# MCU.net
KiCad netlist of a schematic drawn in Altium Designer
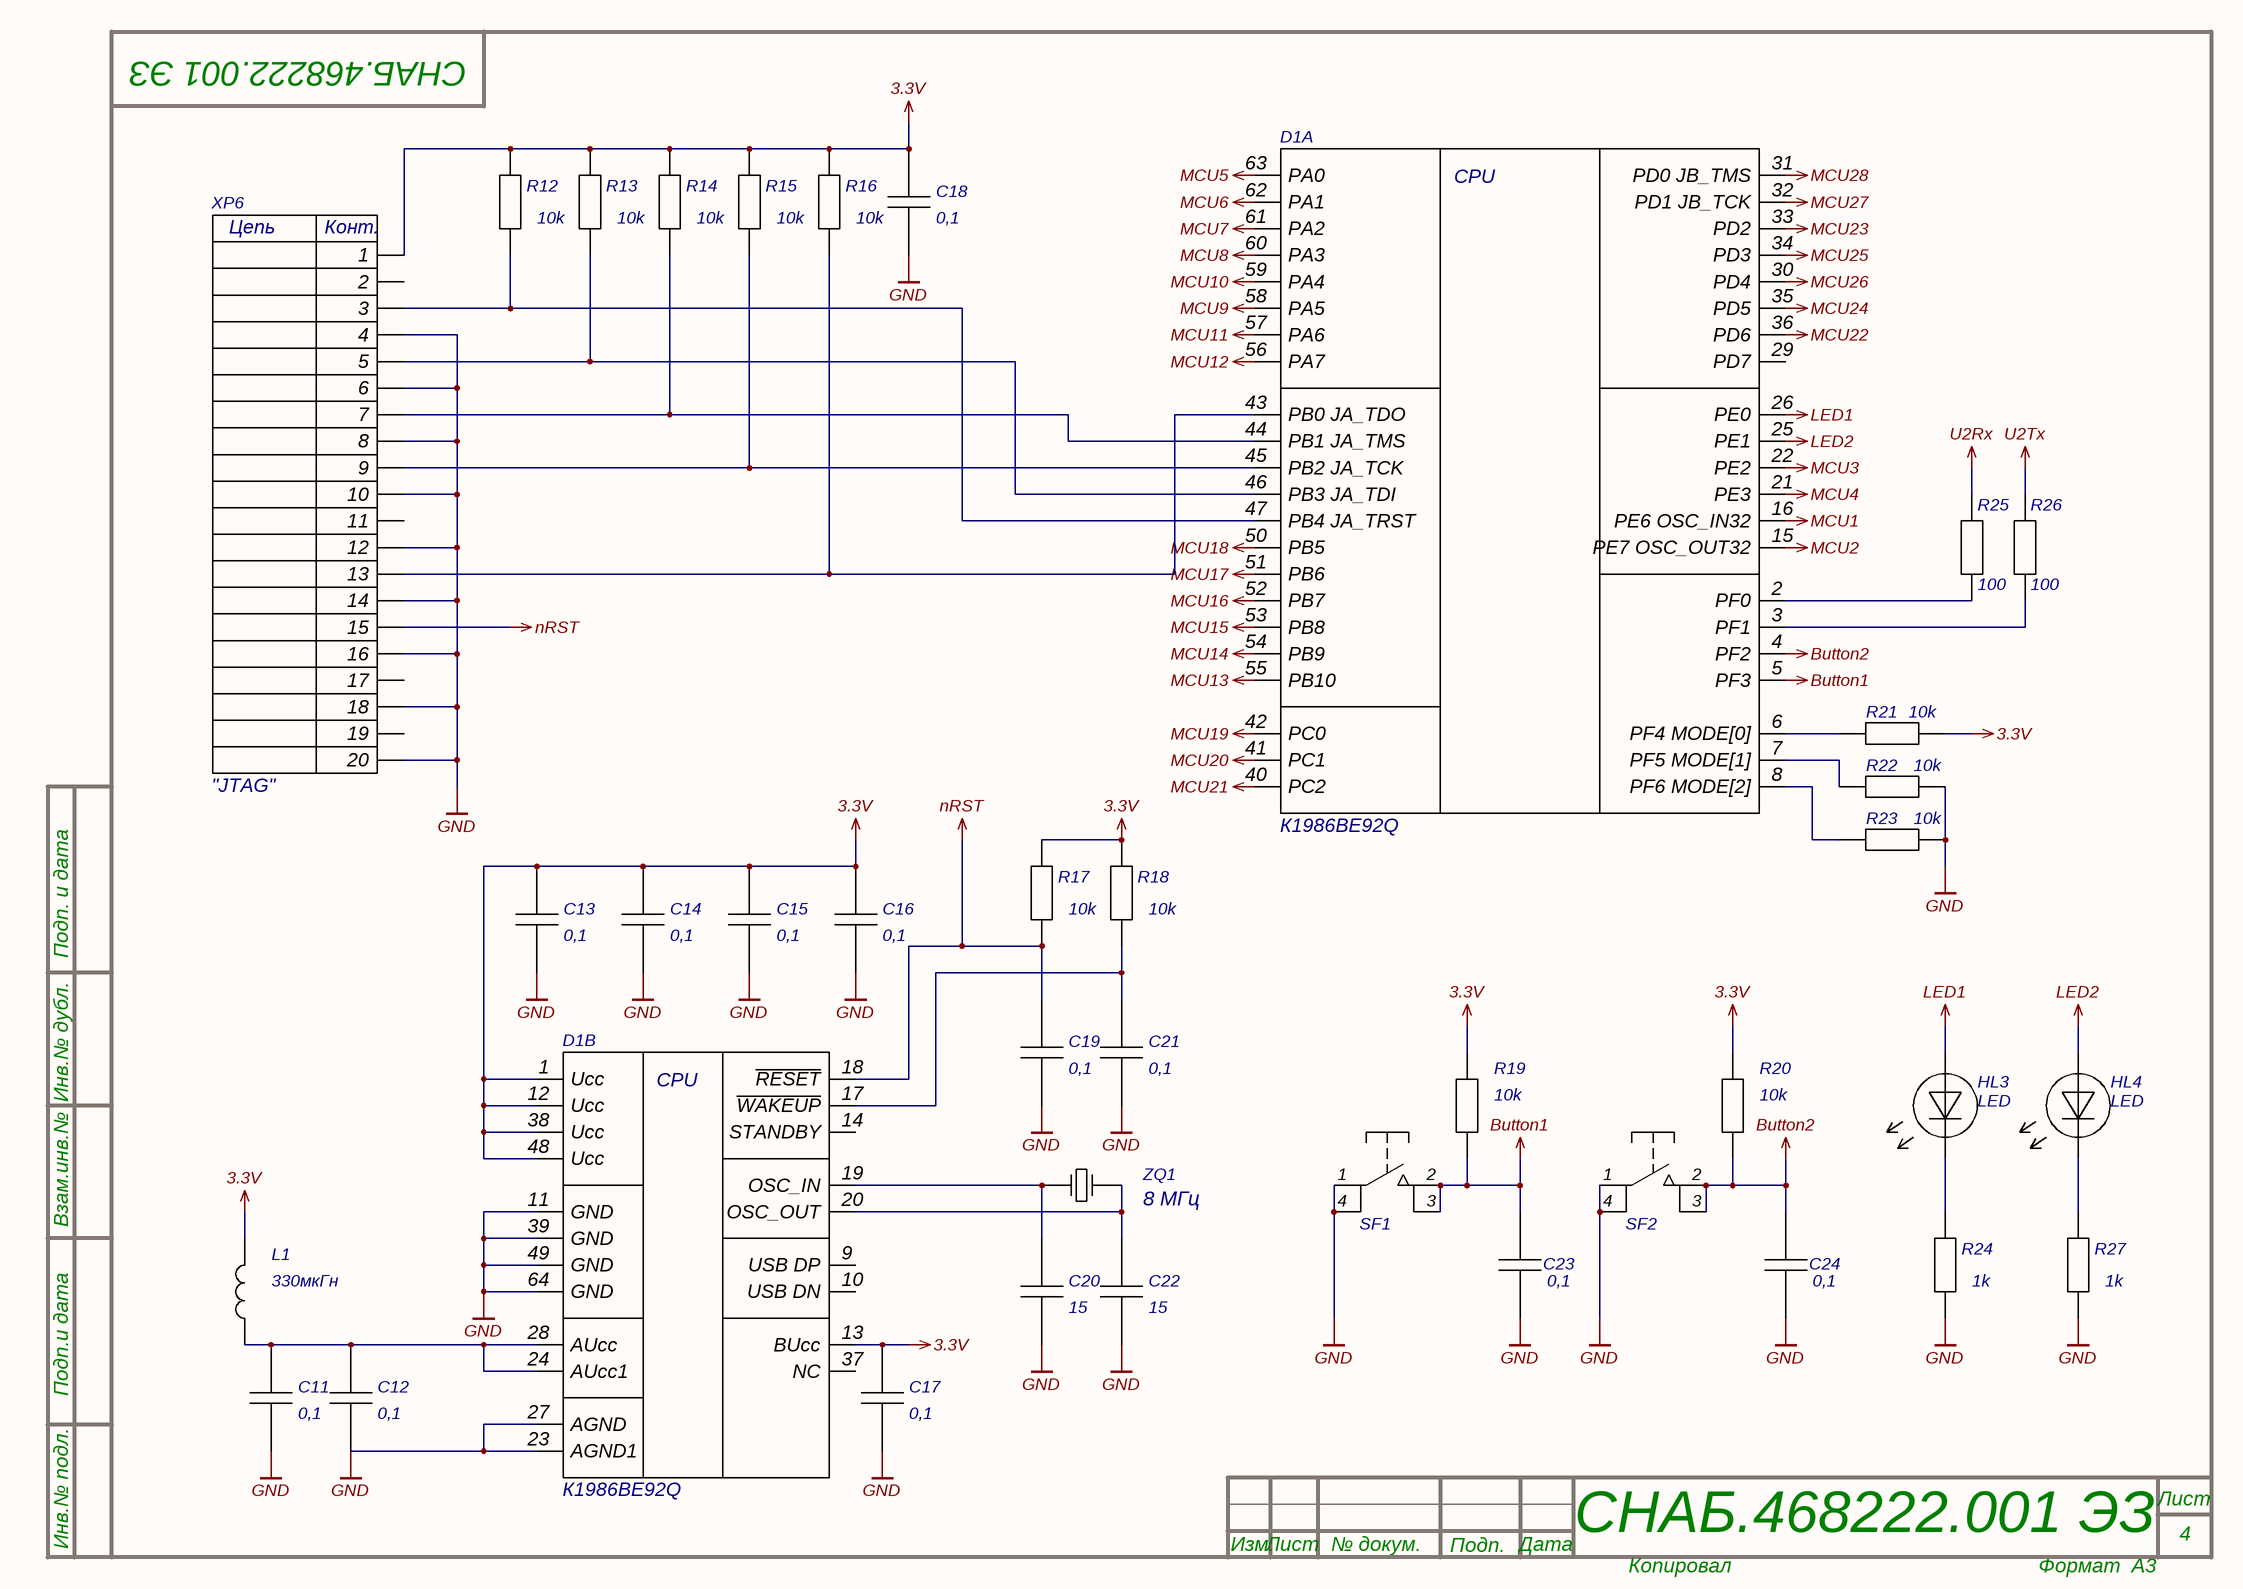
[diagram p0: MCU.SchDoc]

(export (version "E")
  (design (tool "Eeschema 10.0.6"))
  (components
    (comp (ref "C11")
      (value "0,1")
      (footprint "C0603")
      (description "Чип-конденсатор")
      (libsource (lib "Passive") (part "Chip Capasitor"))
    )
    (comp (ref "C12")
      (value "0,1")
      (footprint "C0603")
      (description "Чип-конденсатор")
      (libsource (lib "Passive") (part "Chip Capasitor"))
    )
    (comp (ref "C13")
      (value "0,1")
      (footprint "C0603")
      (description "Чип-конденсатор")
      (libsource (lib "Passive") (part "Chip Capasitor"))
    )
    (comp (ref "C14")
      (value "0,1")
      (footprint "C0603")
      (description "Чип-конденсатор")
      (libsource (lib "Passive") (part "Chip Capasitor"))
    )
    (comp (ref "C15")
      (value "0,1")
      (footprint "C0603")
      (description "Чип-конденсатор")
      (libsource (lib "Passive") (part "Chip Capasitor"))
    )
    (comp (ref "C16")
      (value "0,1")
      (footprint "C0603")
      (description "Чип-конденсатор")
      (libsource (lib "Passive") (part "Chip Capasitor"))
    )
    (comp (ref "C17")
      (value "0,1")
      (footprint "C0603")
      (description "Чип-конденсатор")
      (libsource (lib "Passive") (part "Chip Capasitor"))
    )
    (comp (ref "C18")
      (value "0,1")
      (footprint "C0603")
      (description "Чип-конденсатор")
      (libsource (lib "Passive") (part "Chip Capasitor"))
    )
    (comp (ref "C19")
      (value "0,1")
      (footprint "C0603")
      (description "Чип-конденсатор")
      (libsource (lib "Passive") (part "Chip Capasitor"))
    )
    (comp (ref "C20")
      (value "15")
      (footprint "C0603")
      (description "Чип-конденсатор")
      (libsource (lib "Passive") (part "Chip Capasitor"))
    )
    (comp (ref "C21")
      (value "0,1")
      (footprint "C0603")
      (description "Чип-конденсатор")
      (libsource (lib "Passive") (part "Chip Capasitor"))
    )
    (comp (ref "C22")
      (value "15")
      (footprint "C0603")
      (description "Чип-конденсатор")
      (libsource (lib "Passive") (part "Chip Capasitor"))
    )
    (comp (ref "C23")
      (value "0,1")
      (footprint "C0603")
      (description "Чип-конденсатор")
      (libsource (lib "Passive") (part "Chip Capasitor"))
    )
    (comp (ref "C24")
      (value "0,1")
      (footprint "C0603")
      (description "Чип-конденсатор")
      (libsource (lib "Passive") (part "Chip Capasitor"))
    )
    (comp (ref "D1")
      (value "К1986ВЕ92Q")
      (footprint "LQFP64")
      (description "32бит микроконтроллер CortexM3")
      (fields (field (name "MANUFACTURER") "АО «ПКК Миландр»"))
      (libsource (lib "Schlib") (part "К1986ВЕ92QI(C)_2parts(LQFP64)"))
    )
    (comp (ref "HL3")
      (value "LED")
      (footprint "LED 5mm (L-7113IT)")
      (description "Светодиод, d=5мм")
      (fields (field (name "MANUFACTURER") "Kingbright"))
      (libsource (lib "Schlib") (part "LED"))
    )
    (comp (ref "HL4")
      (value "LED")
      (footprint "LED 5mm (L-7113IT)")
      (description "Светодиод, d=5мм")
      (fields (field (name "MANUFACTURER") "Kingbright"))
      (libsource (lib "Schlib") (part "LED"))
    )
    (comp (ref "L1")
      (value "330мкГн")
      (footprint "LQH43M (1812)")
      (description "Чип-индуктивность 95мА, 330мкГн 10%")
      (fields (field (name "MANUFACTURER") "Murata Electronics"))
      (libsource (lib "Schlib") (part "LQH43MN331K"))
    )
    (comp (ref "R12")
      (value "10k")
      (footprint "R0805")
      (description "Чип-резистор")
      (libsource (lib "Passive") (part "Chip Resistor"))
    )
    (comp (ref "R13")
      (value "10k")
      (footprint "R0805")
      (description "Чип-резистор")
      (libsource (lib "Passive") (part "Chip Resistor"))
    )
    (comp (ref "R14")
      (value "10k")
      (footprint "R0805")
      (description "Чип-резистор")
      (libsource (lib "Passive") (part "Chip Resistor"))
    )
    (comp (ref "R15")
      (value "10k")
      (footprint "R0805")
      (description "Чип-резистор")
      (libsource (lib "Passive") (part "Chip Resistor"))
    )
    (comp (ref "R16")
      (value "10k")
      (footprint "R0805")
      (description "Чип-резистор")
      (libsource (lib "Passive") (part "Chip Resistor"))
    )
    (comp (ref "R17")
      (value "10k")
      (footprint "R0805")
      (description "Чип-резистор")
      (libsource (lib "Passive") (part "Chip Resistor"))
    )
    (comp (ref "R18")
      (value "10k")
      (footprint "R0805")
      (description "Чип-резистор")
      (libsource (lib "Passive") (part "Chip Resistor"))
    )
    (comp (ref "R19")
      (value "10k")
      (footprint "R0603")
      (description "Чип-резистор")
      (libsource (lib "") (part "Chip Resistor_1"))
    )
    (comp (ref "R20")
      (value "10k")
      (footprint "R0603")
      (description "Чип-резистор")
      (libsource (lib "") (part "Chip Resistor_1"))
    )
    (comp (ref "R21")
      (value "10k")
      (footprint "R0805")
      (description "Чип-резистор")
      (libsource (lib "") (part "Chip Resistor_2"))
    )
    (comp (ref "R22")
      (value "10k")
      (footprint "R0805")
      (description "Чип-резистор")
      (libsource (lib "") (part "Chip Resistor_2"))
    )
    (comp (ref "R23")
      (value "10k")
      (footprint "R0805")
      (description "Чип-резистор")
      (libsource (lib "") (part "Chip Resistor_2"))
    )
    (comp (ref "R24")
      (value "1k")
      (footprint "R0805")
      (description "Чип-резистор")
      (libsource (lib "Passive") (part "Chip Resistor"))
    )
    (comp (ref "R25")
      (value "100")
      (footprint "R0805")
      (description "Чип-резистор")
      (libsource (lib "Passive") (part "Chip Resistor"))
    )
    (comp (ref "R26")
      (value "100")
      (footprint "R0805")
      (description "Чип-резистор")
      (libsource (lib "Passive") (part "Chip Resistor"))
    )
    (comp (ref "R27")
      (value "1k")
      (footprint "R0805")
      (description "Чип-резистор")
      (libsource (lib "Passive") (part "Chip Resistor"))
    )
    (comp (ref "SF1")
      (value "0650HIM-130G-G")
      (footprint "TC-0103")
      (description "Кнопка тактовая, h=5мм")
      (fields (field (name "MANUFACTURER") "Switronic Industrial"))
      (libsource (lib "Schlib") (part "0650HIM-130G-G"))
    )
    (comp (ref "SF2")
      (value "0650HIM-130G-G")
      (footprint "TC-0103")
      (description "Кнопка тактовая, h=5мм")
      (fields (field (name "MANUFACTURER") "Switronic Industrial"))
      (libsource (lib "Schlib") (part "0650HIM-130G-G"))
    )
    (comp (ref "XP6")
      (value "\"JTAG\"")
      (footprint "IDC_20")
      (description "J-TAG Connector")
      (libsource (lib "Schlib") (part "JTAG_20 L"))
    )
    (comp (ref "ZQ1")
      (value "8 МГц")
      (footprint "HC-49SM")
      (description "Кварцевый резонатор, 8 МГц")
      (fields (field (name "MANUFACTURER") "SJK"))
      (libsource (lib "Schlib") (part "QuartzRes"))
    )
  )
  (nets
    (net (code "1") (name "3.3V") (class "Default")
      (node (ref "C13") (pin "2") (pinfunction "2_2") (pintype "passive"))
      (node (ref "C14") (pin "2") (pinfunction "2_2") (pintype "passive"))
      (node (ref "C15") (pin "2") (pinfunction "2_2") (pintype "passive"))
      (node (ref "C16") (pin "2") (pinfunction "2_2") (pintype "passive"))
      (node (ref "C17") (pin "2") (pinfunction "2_2") (pintype "passive"))
      (node (ref "C18") (pin "2") (pinfunction "2_2") (pintype "passive"))
      (node (ref "D1") (pin "1") (pinfunction "Ucc_1") (pintype "passive"))
      (node (ref "D1") (pin "12") (pinfunction "Ucc_12") (pintype "passive"))
      (node (ref "D1") (pin "13") (pinfunction "BUcc_13") (pintype "passive"))
      (node (ref "D1") (pin "38") (pinfunction "Ucc_38") (pintype "passive"))
      (node (ref "D1") (pin "48") (pinfunction "Ucc_48") (pintype "passive"))
      (node (ref "L1") (pin "2") (pinfunction "2_2") (pintype "passive"))
      (node (ref "R12") (pin "2") (pinfunction "2_2") (pintype "passive"))
      (node (ref "R13") (pin "2") (pinfunction "2_2") (pintype "passive"))
      (node (ref "R14") (pin "2") (pinfunction "2_2") (pintype "passive"))
      (node (ref "R15") (pin "2") (pinfunction "2_2") (pintype "passive"))
      (node (ref "R16") (pin "2") (pinfunction "2_2") (pintype "passive"))
      (node (ref "R17") (pin "2") (pinfunction "2_2") (pintype "passive"))
      (node (ref "R18") (pin "2") (pinfunction "2_2") (pintype "passive"))
      (node (ref "R19") (pin "1") (pinfunction "1_1") (pintype "passive"))
      (node (ref "R20") (pin "1") (pinfunction "1_1") (pintype "passive"))
      (node (ref "R21") (pin "2") (pinfunction "2_2") (pintype "passive"))
      (node (ref "XP6") (pin "1") (pinfunction "1_1") (pintype "passive"))
    )
    (net (code "2") (name "Button1") (class "Default")
      (node (ref "C23") (pin "2") (pinfunction "2_2") (pintype "passive"))
      (node (ref "D1") (pin "5") (pinfunction "PF3_5") (pintype "passive"))
      (node (ref "R19") (pin "2") (pinfunction "2_2") (pintype "passive"))
      (node (ref "SF1") (pin "2") (pinfunction "2_2") (pintype "passive"))
      (node (ref "SF1") (pin "3") (pinfunction "3_3") (pintype "passive"))
    )
    (net (code "3") (name "Button2") (class "Default")
      (node (ref "C24") (pin "2") (pinfunction "2_2") (pintype "passive"))
      (node (ref "D1") (pin "4") (pinfunction "PF2_4") (pintype "passive"))
      (node (ref "R20") (pin "2") (pinfunction "2_2") (pintype "passive"))
      (node (ref "SF2") (pin "2") (pinfunction "2_2") (pintype "passive"))
      (node (ref "SF2") (pin "3") (pinfunction "3_3") (pintype "passive"))
    )
    (net (code "4") (name "GND") (class "Default")
      (node (ref "C11") (pin "1") (pinfunction "1_1") (pintype "passive"))
      (node (ref "C12") (pin "1") (pinfunction "1_1") (pintype "passive"))
      (node (ref "C13") (pin "1") (pinfunction "1_1") (pintype "passive"))
      (node (ref "C14") (pin "1") (pinfunction "1_1") (pintype "passive"))
      (node (ref "C15") (pin "1") (pinfunction "1_1") (pintype "passive"))
      (node (ref "C16") (pin "1") (pinfunction "1_1") (pintype "passive"))
      (node (ref "C17") (pin "1") (pinfunction "1_1") (pintype "passive"))
      (node (ref "C18") (pin "1") (pinfunction "1_1") (pintype "passive"))
      (node (ref "C19") (pin "1") (pinfunction "1_1") (pintype "passive"))
      (node (ref "C20") (pin "1") (pinfunction "1_1") (pintype "passive"))
      (node (ref "C21") (pin "1") (pinfunction "1_1") (pintype "passive"))
      (node (ref "C22") (pin "1") (pinfunction "1_1") (pintype "passive"))
      (node (ref "C23") (pin "1") (pinfunction "1_1") (pintype "passive"))
      (node (ref "C24") (pin "1") (pinfunction "1_1") (pintype "passive"))
      (node (ref "D1") (pin "11") (pinfunction "GND_11") (pintype "passive"))
      (node (ref "D1") (pin "23") (pinfunction "AGND1_23") (pintype "passive"))
      (node (ref "D1") (pin "27") (pinfunction "AGND_27") (pintype "passive"))
      (node (ref "D1") (pin "39") (pinfunction "GND_39") (pintype "passive"))
      (node (ref "D1") (pin "49") (pinfunction "GND_49") (pintype "passive"))
      (node (ref "D1") (pin "64") (pinfunction "GND_64") (pintype "passive"))
      (node (ref "R22") (pin "2") (pinfunction "2_2") (pintype "passive"))
      (node (ref "R23") (pin "2") (pinfunction "2_2") (pintype "passive"))
      (node (ref "R24") (pin "1") (pinfunction "1_1") (pintype "passive"))
      (node (ref "R27") (pin "1") (pinfunction "1_1") (pintype "passive"))
      (node (ref "SF1") (pin "1") (pinfunction "1_1") (pintype "passive"))
      (node (ref "SF1") (pin "4") (pinfunction "4_4") (pintype "passive"))
      (node (ref "SF2") (pin "1") (pinfunction "1_1") (pintype "passive"))
      (node (ref "SF2") (pin "4") (pinfunction "4_4") (pintype "passive"))
      (node (ref "XP6") (pin "10") (pinfunction "10_10") (pintype "passive"))
      (node (ref "XP6") (pin "12") (pinfunction "12_12") (pintype "passive"))
      (node (ref "XP6") (pin "14") (pinfunction "14_14") (pintype "passive"))
      (node (ref "XP6") (pin "16") (pinfunction "16_16") (pintype "passive"))
      (node (ref "XP6") (pin "18") (pinfunction "18_18") (pintype "passive"))
      (node (ref "XP6") (pin "20") (pinfunction "20_20") (pintype "passive"))
      (node (ref "XP6") (pin "4") (pinfunction "4_4") (pintype "passive"))
      (node (ref "XP6") (pin "6") (pinfunction "6_6") (pintype "passive"))
      (node (ref "XP6") (pin "8") (pinfunction "8_8") (pintype "passive"))
    )
    (net (code "5") (name "LED1") (class "Default")
      (node (ref "D1") (pin "26") (pinfunction "PE0_26") (pintype "passive"))
      (node (ref "HL3") (pin "2") (pinfunction "A_2") (pintype "passive"))
    )
    (net (code "6") (name "LED2") (class "Default")
      (node (ref "D1") (pin "25") (pinfunction "PE1_25") (pintype "passive"))
      (node (ref "HL4") (pin "2") (pinfunction "A_2") (pintype "passive"))
    )
    (net (code "7") (name "MCU1") (class "Default")
      (node (ref "D1") (pin "16") (pinfunction "PE6_OSC_IN32_16") (pintype "passive"))
    )
    (net (code "8") (name "MCU2") (class "Default")
      (node (ref "D1") (pin "15") (pinfunction "PE7_OSC_OUT32_15") (pintype "passive"))
    )
    (net (code "9") (name "MCU3") (class "Default")
      (node (ref "D1") (pin "22") (pinfunction "PE2_22") (pintype "passive"))
    )
    (net (code "10") (name "MCU4") (class "Default")
      (node (ref "D1") (pin "21") (pinfunction "PE3_21") (pintype "passive"))
    )
    (net (code "11") (name "MCU5") (class "Default")
      (node (ref "D1") (pin "63") (pinfunction "PA0_63") (pintype "passive"))
    )
    (net (code "12") (name "MCU6") (class "Default")
      (node (ref "D1") (pin "62") (pinfunction "PA1_62") (pintype "passive"))
    )
    (net (code "13") (name "MCU7") (class "Default")
      (node (ref "D1") (pin "61") (pinfunction "PA2_61") (pintype "passive"))
    )
    (net (code "14") (name "MCU8") (class "Default")
      (node (ref "D1") (pin "60") (pinfunction "PA3_60") (pintype "passive"))
    )
    (net (code "15") (name "MCU9") (class "Default")
      (node (ref "D1") (pin "58") (pinfunction "PA5_58") (pintype "passive"))
    )
    (net (code "16") (name "MCU10") (class "Default")
      (node (ref "D1") (pin "59") (pinfunction "PA4_59") (pintype "passive"))
    )
    (net (code "17") (name "MCU11") (class "Default")
      (node (ref "D1") (pin "57") (pinfunction "PA6_57") (pintype "passive"))
    )
    (net (code "18") (name "MCU12") (class "Default")
      (node (ref "D1") (pin "56") (pinfunction "PA7_56") (pintype "passive"))
    )
    (net (code "19") (name "MCU13") (class "Default")
      (node (ref "D1") (pin "55") (pinfunction "PB10_55") (pintype "passive"))
    )
    (net (code "20") (name "MCU14") (class "Default")
      (node (ref "D1") (pin "54") (pinfunction "PB9_54") (pintype "passive"))
    )
    (net (code "21") (name "MCU15") (class "Default")
      (node (ref "D1") (pin "53") (pinfunction "PB8_53") (pintype "passive"))
    )
    (net (code "22") (name "MCU16") (class "Default")
      (node (ref "D1") (pin "52") (pinfunction "PB7_52") (pintype "passive"))
    )
    (net (code "23") (name "MCU17") (class "Default")
      (node (ref "D1") (pin "51") (pinfunction "PB6_51") (pintype "passive"))
    )
    (net (code "24") (name "MCU18") (class "Default")
      (node (ref "D1") (pin "50") (pinfunction "PB5_50") (pintype "passive"))
    )
    (net (code "25") (name "MCU19") (class "Default")
      (node (ref "D1") (pin "42") (pinfunction "PC0_42") (pintype "passive"))
    )
    (net (code "26") (name "MCU20") (class "Default")
      (node (ref "D1") (pin "41") (pinfunction "PC1_41") (pintype "passive"))
    )
    (net (code "27") (name "MCU21") (class "Default")
      (node (ref "D1") (pin "40") (pinfunction "PC2_40") (pintype "passive"))
    )
    (net (code "28") (name "MCU22") (class "Default")
      (node (ref "D1") (pin "36") (pinfunction "PD6_36") (pintype "passive"))
    )
    (net (code "29") (name "MCU23") (class "Default")
      (node (ref "D1") (pin "33") (pinfunction "PD2_33") (pintype "passive"))
    )
    (net (code "30") (name "MCU24") (class "Default")
      (node (ref "D1") (pin "35") (pinfunction "PD5_35") (pintype "passive"))
    )
    (net (code "31") (name "MCU25") (class "Default")
      (node (ref "D1") (pin "34") (pinfunction "PD3_34") (pintype "passive"))
    )
    (net (code "32") (name "MCU26") (class "Default")
      (node (ref "D1") (pin "30") (pinfunction "PD4_30") (pintype "passive"))
    )
    (net (code "33") (name "MCU27") (class "Default")
      (node (ref "D1") (pin "32") (pinfunction "PD1_JB_TCK_32") (pintype "passive"))
    )
    (net (code "34") (name "MCU28") (class "Default")
      (node (ref "D1") (pin "31") (pinfunction "PD0_JB_TMS_31") (pintype "passive"))
    )
    (net (code "35") (name "Net-(D1A-PB0_JA_TDO)") (class "Default")
      (node (ref "D1") (pin "43") (pinfunction "PB0_JA_TDO_43") (pintype "passive"))
      (node (ref "R16") (pin "1") (pinfunction "1_1") (pintype "passive"))
      (node (ref "XP6") (pin "13") (pinfunction "13_13") (pintype "passive"))
    )
    (net (code "36") (name "Net-(D1A-PB1_JA_TMS)") (class "Default")
      (node (ref "D1") (pin "44") (pinfunction "PB1_JA_TMS_44") (pintype "passive"))
      (node (ref "R14") (pin "1") (pinfunction "1_1") (pintype "passive"))
      (node (ref "XP6") (pin "7") (pinfunction "7_7") (pintype "passive"))
    )
    (net (code "37") (name "Net-(D1A-PB2_JA_TCK)") (class "Default")
      (node (ref "D1") (pin "45") (pinfunction "PB2_JA_TCK_45") (pintype "passive"))
      (node (ref "R15") (pin "1") (pinfunction "1_1") (pintype "passive"))
      (node (ref "XP6") (pin "9") (pinfunction "9_9") (pintype "passive"))
    )
    (net (code "38") (name "Net-(D1A-PB3_JA_TDI)") (class "Default")
      (node (ref "D1") (pin "46") (pinfunction "PB3_JA_TDI_46") (pintype "passive"))
      (node (ref "R13") (pin "1") (pinfunction "1_1") (pintype "passive"))
      (node (ref "XP6") (pin "5") (pinfunction "5_5") (pintype "passive"))
    )
    (net (code "39") (name "Net-(D1A-PB4_JA_TRST)") (class "Default")
      (node (ref "D1") (pin "47") (pinfunction "PB4_JA_TRST_47") (pintype "passive"))
      (node (ref "R12") (pin "1") (pinfunction "1_1") (pintype "passive"))
      (node (ref "XP6") (pin "3") (pinfunction "3_3") (pintype "passive"))
    )
    (net (code "40") (name "Net-(D1A-PF0)") (class "Default")
      (node (ref "D1") (pin "2") (pinfunction "PF0_2") (pintype "passive"))
      (node (ref "R25") (pin "1") (pinfunction "1_1") (pintype "passive"))
    )
    (net (code "41") (name "Net-(D1A-PF1)") (class "Default")
      (node (ref "D1") (pin "3") (pinfunction "PF1_3") (pintype "passive"))
      (node (ref "R26") (pin "1") (pinfunction "1_1") (pintype "passive"))
    )
    (net (code "42") (name "Net-(D1A-PF4_MODE[0])") (class "Default")
      (node (ref "D1") (pin "6") (pinfunction "PF4_MODE[0]_6") (pintype "passive"))
      (node (ref "R21") (pin "1") (pinfunction "1_1") (pintype "passive"))
    )
    (net (code "43") (name "Net-(D1A-PF5_MODE[1])") (class "Default")
      (node (ref "D1") (pin "7") (pinfunction "PF5_MODE[1]_7") (pintype "passive"))
      (node (ref "R22") (pin "1") (pinfunction "1_1") (pintype "passive"))
    )
    (net (code "44") (name "Net-(D1A-PF6_MODE[2])") (class "Default")
      (node (ref "D1") (pin "8") (pinfunction "PF6_MODE[2]_8") (pintype "passive"))
      (node (ref "R23") (pin "1") (pinfunction "1_1") (pintype "passive"))
    )
    (net (code "45") (name "Net-(D1B-AUcc)") (class "Default")
      (node (ref "C11") (pin "2") (pinfunction "2_2") (pintype "passive"))
      (node (ref "C12") (pin "2") (pinfunction "2_2") (pintype "passive"))
      (node (ref "D1") (pin "24") (pinfunction "AUcc1_24") (pintype "passive"))
      (node (ref "D1") (pin "28") (pinfunction "AUcc_28") (pintype "passive"))
      (node (ref "L1") (pin "1") (pinfunction "1_1") (pintype "passive"))
    )
    (net (code "46") (name "Net-(D1B-OSC_IN)") (class "Default")
      (node (ref "C20") (pin "2") (pinfunction "2_2") (pintype "passive"))
      (node (ref "D1") (pin "19") (pinfunction "OSC_IN_19") (pintype "passive"))
      (node (ref "ZQ1") (pin "1") (pinfunction "1_1") (pintype "passive"))
    )
    (net (code "47") (name "Net-(D1B-OSC_OUT)") (class "Default")
      (node (ref "C22") (pin "2") (pinfunction "2_2") (pintype "passive"))
      (node (ref "D1") (pin "20") (pinfunction "OSC_OUT_20") (pintype "passive"))
      (node (ref "ZQ1") (pin "2") (pinfunction "2_2") (pintype "passive"))
    )
    (net (code "48") (name "Net-(D1B-~{WAKEUP})") (class "Default")
      (node (ref "C21") (pin "2") (pinfunction "2_2") (pintype "passive"))
      (node (ref "D1") (pin "17") (pinfunction "~{WAKEUP}_17") (pintype "passive"))
      (node (ref "R18") (pin "1") (pinfunction "1_1") (pintype "passive"))
    )
    (net (code "49") (name "Net-(HL3-K)") (class "Default")
      (node (ref "HL3") (pin "1") (pinfunction "K_1") (pintype "passive"))
      (node (ref "R24") (pin "2") (pinfunction "2_2") (pintype "passive"))
    )
    (net (code "50") (name "Net-(HL4-K)") (class "Default")
      (node (ref "HL4") (pin "1") (pinfunction "K_1") (pintype "passive"))
      (node (ref "R27") (pin "2") (pinfunction "2_2") (pintype "passive"))
    )
    (net (code "51") (name "U2Rx") (class "Default")
      (node (ref "R25") (pin "2") (pinfunction "2_2") (pintype "passive"))
    )
    (net (code "52") (name "U2Tx") (class "Default")
      (node (ref "R26") (pin "2") (pinfunction "2_2") (pintype "passive"))
    )
    (net (code "53") (name "nRST") (class "Default")
      (node (ref "C19") (pin "2") (pinfunction "2_2") (pintype "passive"))
      (node (ref "D1") (pin "18") (pinfunction "~{RESET}_18") (pintype "passive"))
      (node (ref "R17") (pin "1") (pinfunction "1_1") (pintype "passive"))
      (node (ref "XP6") (pin "15") (pinfunction "15_15") (pintype "passive"))
    )
    (net (code "54") (name "unconnected-(D1A-PD7-Pad29)") (class "Default")
      (node (ref "D1") (pin "29") (pinfunction "PD7_29") (pintype "passive"))
    )
    (net (code "55") (name "unconnected-(D1B-NC-Pad37)") (class "Default")
      (node (ref "D1") (pin "37") (pinfunction "NC_37") (pintype "passive"))
    )
    (net (code "56") (name "unconnected-(D1B-STANDBY-Pad14)") (class "Default")
      (node (ref "D1") (pin "14") (pinfunction "STANDBY_14") (pintype "passive"))
    )
    (net (code "57") (name "unconnected-(D1B-USB_DN-Pad10)") (class "Default")
      (node (ref "D1") (pin "10") (pinfunction "USB_DN_10") (pintype "passive"))
    )
    (net (code "58") (name "unconnected-(D1B-USB_DP-Pad9)") (class "Default")
      (node (ref "D1") (pin "9") (pinfunction "USB_DP_9") (pintype "passive"))
    )
    (net (code "59") (name "unconnected-(XP6-Pad2)") (class "Default")
      (node (ref "XP6") (pin "2") (pinfunction "2_2") (pintype "passive"))
    )
    (net (code "60") (name "unconnected-(XP6-Pad11)") (class "Default")
      (node (ref "XP6") (pin "11") (pinfunction "11_11") (pintype "passive"))
    )
    (net (code "61") (name "unconnected-(XP6-Pad17)") (class "Default")
      (node (ref "XP6") (pin "17") (pinfunction "17_17") (pintype "passive"))
    )
    (net (code "62") (name "unconnected-(XP6-Pad19)") (class "Default")
      (node (ref "XP6") (pin "19") (pinfunction "19_19") (pintype "passive"))
    )
  )
)
